# fabflash-mk-2-booster.net
KiCad netlist of a schematic drawn in EAGLE
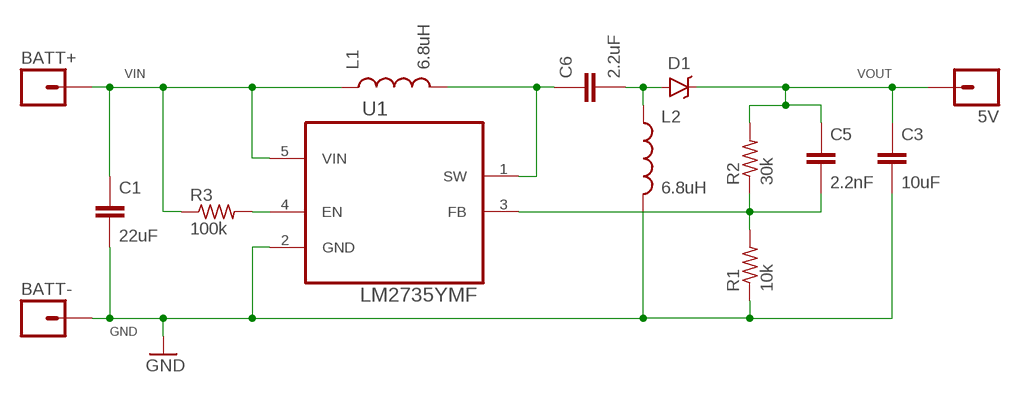
[diagram p0: schematic, sheet 1]

(export (version "E")
  (design (tool "Eeschema 10.0.6"))
  (components
    (comp (ref "5V")
      (value "M01PTH-1.2MM")
      (footprint "eagle-import:1X01-1.2MM")
      (libsource (lib "eagle-import") (part "M01PTH-1.2MM"))
    )
    (comp (ref "BATT+")
      (value "M01NOT-A-VIA-NOPE")
      (footprint "eagle-import:1X01_NOSILK_NOSTOP")
      (libsource (lib "eagle-import") (part "M01NOT-A-VIA-NOPE"))
    )
    (comp (ref "BATT-")
      (value "M01NOT-A-VIA-NOPE")
      (footprint "eagle-import:1X01_NOSILK_NOSTOP")
      (libsource (lib "eagle-import") (part "M01NOT-A-VIA-NOPE"))
    )
    (comp (ref "C1")
      (value "22uF")
      (footprint "eagle-import:C0805")
      (libsource (lib "eagle-import") (part "CAPACITOR-CERAMICC0805"))
    )
    (comp (ref "C3")
      (value "10uF")
      (footprint "eagle-import:C0805")
      (libsource (lib "eagle-import") (part "CAPACITOR-CERAMICC0805"))
    )
    (comp (ref "C5")
      (value "2.2nF")
      (footprint "eagle-import:C0805")
      (libsource (lib "eagle-import") (part "CAPACITOR-CERAMICC0805"))
    )
    (comp (ref "C6")
      (value "2.2uF")
      (footprint "eagle-import:C0805")
      (libsource (lib "eagle-import") (part "CAPACITOR-CERAMICC0805"))
    )
    (comp (ref "D1")
      (value "B340A")
      (footprint "eagle-import:SMA-DIODE")
      (libsource (lib "eagle-import") (part "DIODE-SCHOTTKYB340A"))
    )
    (comp (ref "L1")
      (value "6.8uH")
      (footprint "eagle-import:TAIYO-YUDEN-40XX")
      (libsource (lib "eagle-import") (part "INDUCTORTAIYO-YUDEN-40XX"))
    )
    (comp (ref "L2")
      (value "6.8uH")
      (footprint "eagle-import:TAIYO-YUDEN-40XX")
      (libsource (lib "eagle-import") (part "INDUCTORTAIYO-YUDEN-40XX"))
    )
    (comp (ref "R1")
      (value "10k")
      (footprint "eagle-import:R0805")
      (libsource (lib "eagle-import") (part "RESISTORR0805"))
    )
    (comp (ref "R2")
      (value "30k")
      (footprint "eagle-import:R0805")
      (libsource (lib "eagle-import") (part "RESISTORR0805"))
    )
    (comp (ref "R3")
      (value "100k")
      (footprint "eagle-import:R0805")
      (libsource (lib "eagle-import") (part "RESISTORR0805"))
    )
    (comp (ref "U1")
      (value "LM2735YMF")
      (footprint "eagle-import:SOT95P285X110-5N")
      (libsource (lib "eagle-import") (part "LM2735YMF"))
    )
  )
  (nets
    (net (code "1") (name "/VIN") (class "Default")
      (node (ref "BATT+") (pin "P$1") (pinfunction "1_P$1") (pintype "passive"))
      (node (ref "C1") (pin "1") (pinfunction "1_1") (pintype "passive"))
      (node (ref "L1") (pin "1") (pinfunction "1_1") (pintype "passive"))
      (node (ref "R3") (pin "1") (pinfunction "1_1") (pintype "passive"))
      (node (ref "U1") (pin "5") (pinfunction "VIN_5") (pintype "power_in"))
    )
    (net (code "2") (name "/VOUT") (class "Default")
      (node (ref "5V") (pin "P$1") (pinfunction "1_P$1") (pintype "passive"))
      (node (ref "C3") (pin "1") (pinfunction "1_1") (pintype "passive"))
      (node (ref "C5") (pin "1") (pinfunction "1_1") (pintype "passive"))
      (node (ref "D1") (pin "C") (pinfunction "C_C") (pintype "passive"))
      (node (ref "R2") (pin "2") (pinfunction "2_2") (pintype "passive"))
    )
    (net (code "3") (name "GND") (class "Default")
      (node (ref "BATT-") (pin "P$1") (pinfunction "1_P$1") (pintype "passive"))
      (node (ref "C1") (pin "2") (pinfunction "2_2") (pintype "passive"))
      (node (ref "C3") (pin "2") (pinfunction "2_2") (pintype "passive"))
      (node (ref "L2") (pin "2") (pinfunction "2_2") (pintype "passive"))
      (node (ref "R1") (pin "1") (pinfunction "1_1") (pintype "passive"))
      (node (ref "U1") (pin "2") (pinfunction "GND_2") (pintype "power_in"))
    )
    (net (code "4") (name "Net-(C6-Pad2)") (class "Default")
      (node (ref "C6") (pin "2") (pinfunction "2_2") (pintype "passive"))
      (node (ref "D1") (pin "A") (pinfunction "A_A") (pintype "passive"))
      (node (ref "L2") (pin "1") (pinfunction "1_1") (pintype "passive"))
    )
    (net (code "5") (name "Net-(U1-EN)") (class "Default")
      (node (ref "R3") (pin "2") (pinfunction "2_2") (pintype "passive"))
      (node (ref "U1") (pin "4") (pinfunction "EN_4") (pintype "input"))
    )
    (net (code "6") (name "Net-(U1-FB)") (class "Default")
      (node (ref "C5") (pin "2") (pinfunction "2_2") (pintype "passive"))
      (node (ref "R1") (pin "2") (pinfunction "2_2") (pintype "passive"))
      (node (ref "R2") (pin "1") (pinfunction "1_1") (pintype "passive"))
      (node (ref "U1") (pin "3") (pinfunction "FB_3") (pintype "input"))
    )
    (net (code "7") (name "Net-(U1-SW)") (class "Default")
      (node (ref "C6") (pin "1") (pinfunction "1_1") (pintype "passive"))
      (node (ref "L1") (pin "2") (pinfunction "2_2") (pintype "passive"))
      (node (ref "U1") (pin "1") (pinfunction "SW_1") (pintype "power_in"))
    )
  )
)
